# Frontpanel.net
KiCad netlist of a schematic drawn in Altium Designer
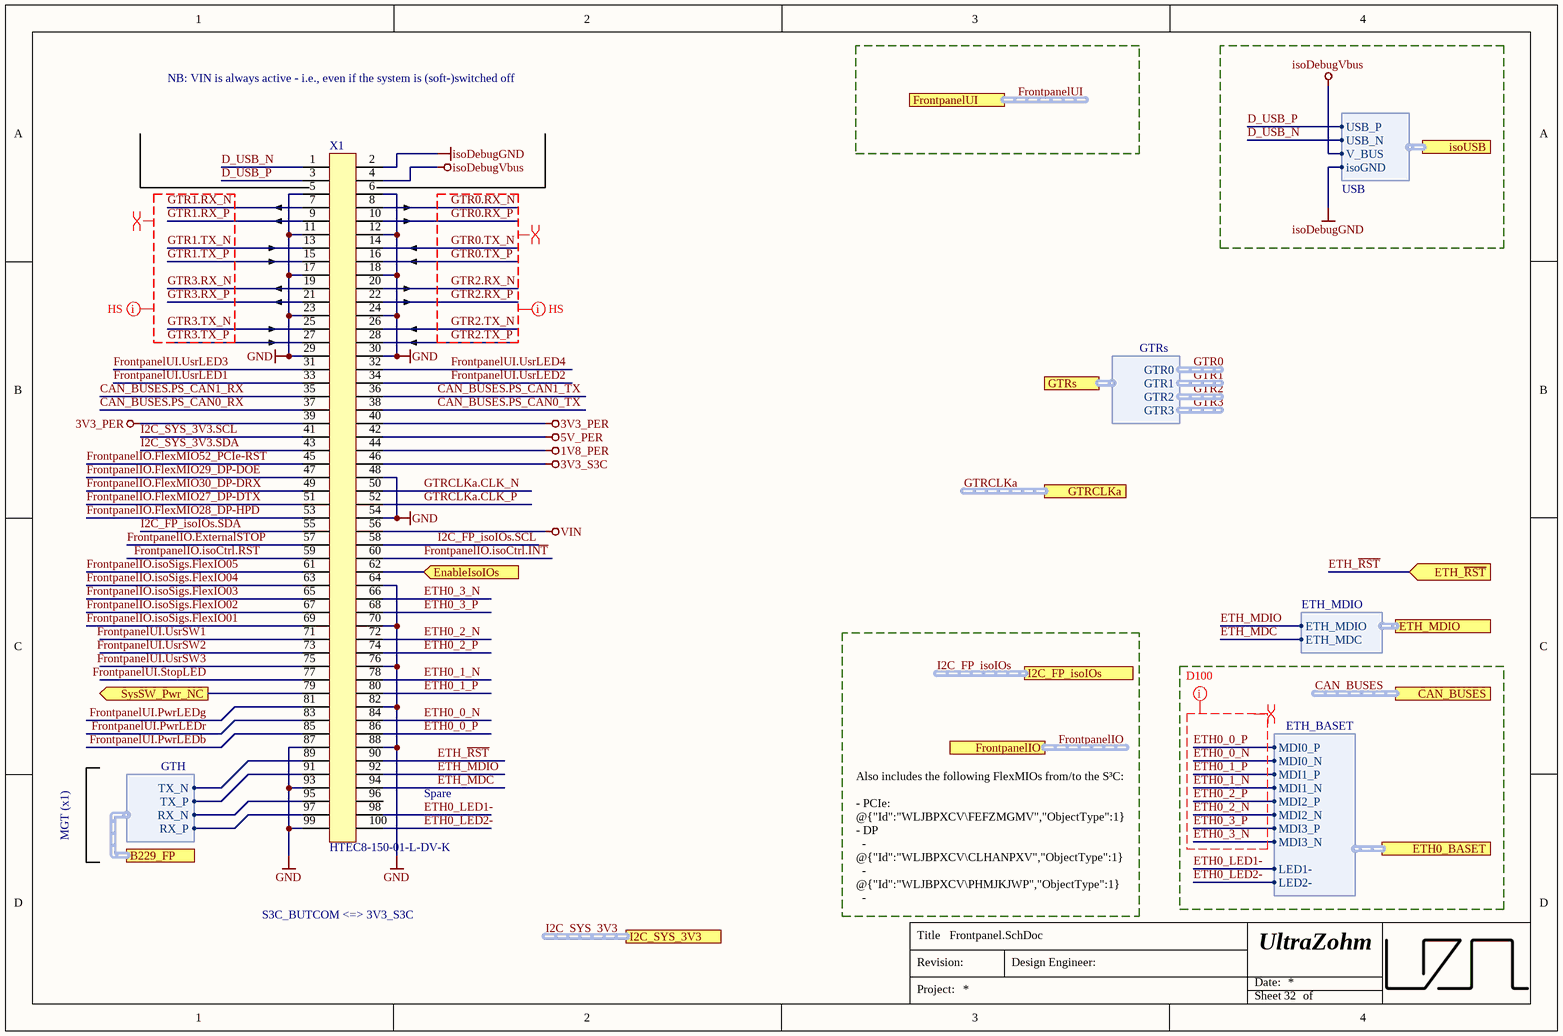
[diagram p0: Frontpanel.SchDoc]

(export (version "E")
  (design (tool "Eeschema 10.0.6"))
  (components
    (comp (ref "X1")
      (value "HTEC8-150-01-L-DV-K")
      (footprint "HTEC8-150-XX-X-DV")
      (description "HTEC8-150-01-L-DV-K mating connector for card layout")
      (fields
        (field (name "MANUFACTURER") "SAMTEC")
        (field (name "LCSC PART NUMBER") "C20365621")
        (field (name "CREATED FROM") "MGremer")
      )
      (libsource (lib "user") (part "HTEC8-150-01-L-DV-K"))
    )
  )
  (nets
    (net (code "14") (name "/CAN_BUSES.PS_CAN0_RX") (class "Default")
      (node (ref "X1") (pin "37") (pinfunction "37_37") (pintype "passive"))
    )
    (net (code "15") (name "/CAN_BUSES.PS_CAN0_TX") (class "Default")
      (node (ref "X1") (pin "38") (pinfunction "38_38") (pintype "passive"))
    )
    (net (code "16") (name "/CAN_BUSES.PS_CAN1_RX") (class "Default")
      (node (ref "X1") (pin "35") (pinfunction "35_35") (pintype "passive"))
    )
    (net (code "17") (name "/CAN_BUSES.PS_CAN1_TX") (class "Default")
      (node (ref "X1") (pin "36") (pinfunction "36_36") (pintype "passive"))
    )
    (net (code "18") (name "/D_USB_N") (class "Default")
      (node (ref "X1") (pin "1") (pinfunction "1_1") (pintype "passive"))
    )
    (net (code "19") (name "/D_USB_P") (class "Default")
      (node (ref "X1") (pin "3") (pinfunction "3_3") (pintype "passive"))
    )
    (net (code "20") (name "/ETH0_0_N") (class "Default")
      (node (ref "X1") (pin "84") (pinfunction "84_84") (pintype "passive"))
    )
    (net (code "21") (name "/ETH0_0_P") (class "Default")
      (node (ref "X1") (pin "86") (pinfunction "86_86") (pintype "passive"))
    )
    (net (code "22") (name "/ETH0_1_N") (class "Default")
      (node (ref "X1") (pin "78") (pinfunction "78_78") (pintype "passive"))
    )
    (net (code "23") (name "/ETH0_1_P") (class "Default")
      (node (ref "X1") (pin "80") (pinfunction "80_80") (pintype "passive"))
    )
    (net (code "24") (name "/ETH0_2_N") (class "Default")
      (node (ref "X1") (pin "72") (pinfunction "72_72") (pintype "passive"))
    )
    (net (code "25") (name "/ETH0_2_P") (class "Default")
      (node (ref "X1") (pin "74") (pinfunction "74_74") (pintype "passive"))
    )
    (net (code "26") (name "/ETH0_3_N") (class "Default")
      (node (ref "X1") (pin "66") (pinfunction "66_66") (pintype "passive"))
    )
    (net (code "27") (name "/ETH0_3_P") (class "Default")
      (node (ref "X1") (pin "68") (pinfunction "68_68") (pintype "passive"))
    )
    (net (code "28") (name "/ETH0_LED1-") (class "Default")
      (node (ref "X1") (pin "98") (pinfunction "98_98") (pintype "passive"))
    )
    (net (code "29") (name "/ETH0_LED2-") (class "Default")
      (node (ref "X1") (pin "100") (pinfunction "100_100") (pintype "passive"))
    )
    (net (code "30") (name "/ETH_MDC") (class "Default")
      (node (ref "X1") (pin "94") (pinfunction "94_94") (pintype "passive"))
    )
    (net (code "31") (name "/ETH_MDIO") (class "Default")
      (node (ref "X1") (pin "92") (pinfunction "92_92") (pintype "passive"))
    )
    (net (code "32") (name "/ETH_~{RST}") (class "Default")
      (node (ref "X1") (pin "90") (pinfunction "90_90") (pintype "passive"))
    )
    (net (code "33") (name "/EnableIsoIOs") (class "Default")
      (node (ref "X1") (pin "62") (pinfunction "62_62") (pintype "passive"))
    )
    (net (code "34") (name "/FrontpanelIO.ExternalSTOP") (class "Default")
      (node (ref "X1") (pin "57") (pinfunction "57_57") (pintype "passive"))
    )
    (net (code "35") (name "/FrontpanelIO.FlexMIO27_DP-DTX") (class "Default")
      (node (ref "X1") (pin "51") (pinfunction "51_51") (pintype "passive"))
    )
    (net (code "36") (name "/FrontpanelIO.FlexMIO28_DP-HPD") (class "Default")
      (node (ref "X1") (pin "53") (pinfunction "53_53") (pintype "passive"))
    )
    (net (code "37") (name "/FrontpanelIO.FlexMIO29_DP-DOE") (class "Default")
      (node (ref "X1") (pin "47") (pinfunction "47_47") (pintype "passive"))
    )
    (net (code "38") (name "/FrontpanelIO.FlexMIO30_DP-DRX") (class "Default")
      (node (ref "X1") (pin "49") (pinfunction "49_49") (pintype "passive"))
    )
    (net (code "39") (name "/FrontpanelIO.FlexMIO52_PCIe-~{RST}") (class "Default")
      (node (ref "X1") (pin "45") (pinfunction "45_45") (pintype "passive"))
    )
    (net (code "40") (name "/FrontpanelIO.isoCtrl.~{INT}") (class "Default")
      (node (ref "X1") (pin "60") (pinfunction "60_60") (pintype "passive"))
    )
    (net (code "41") (name "/FrontpanelIO.isoCtrl.~{RST}") (class "Default")
      (node (ref "X1") (pin "59") (pinfunction "59_59") (pintype "passive"))
    )
    (net (code "42") (name "/FrontpanelIO.isoSigs.FlexIO01") (class "Default")
      (node (ref "X1") (pin "69") (pinfunction "69_69") (pintype "passive"))
    )
    (net (code "43") (name "/FrontpanelIO.isoSigs.FlexIO02") (class "Default")
      (node (ref "X1") (pin "67") (pinfunction "67_67") (pintype "passive"))
    )
    (net (code "44") (name "/FrontpanelIO.isoSigs.FlexIO03") (class "Default")
      (node (ref "X1") (pin "65") (pinfunction "65_65") (pintype "passive"))
    )
    (net (code "45") (name "/FrontpanelIO.isoSigs.FlexIO04") (class "Default")
      (node (ref "X1") (pin "63") (pinfunction "63_63") (pintype "passive"))
    )
    (net (code "46") (name "/FrontpanelIO.isoSigs.FlexIO05") (class "Default")
      (node (ref "X1") (pin "61") (pinfunction "61_61") (pintype "passive"))
    )
    (net (code "47") (name "/FrontpanelUI.PwrLEDb") (class "Default")
      (node (ref "X1") (pin "85") (pinfunction "85_85") (pintype "passive"))
    )
    (net (code "48") (name "/FrontpanelUI.PwrLEDg") (class "Default")
      (node (ref "X1") (pin "81") (pinfunction "81_81") (pintype "passive"))
    )
    (net (code "49") (name "/FrontpanelUI.PwrLEDr") (class "Default")
      (node (ref "X1") (pin "83") (pinfunction "83_83") (pintype "passive"))
    )
    (net (code "50") (name "/FrontpanelUI.StopLED") (class "Default")
      (node (ref "X1") (pin "77") (pinfunction "77_77") (pintype "passive"))
    )
    (net (code "51") (name "/FrontpanelUI.UsrLED1") (class "Default")
      (node (ref "X1") (pin "33") (pinfunction "33_33") (pintype "passive"))
    )
    (net (code "52") (name "/FrontpanelUI.UsrLED2") (class "Default")
      (node (ref "X1") (pin "34") (pinfunction "34_34") (pintype "passive"))
    )
    (net (code "53") (name "/FrontpanelUI.UsrLED3") (class "Default")
      (node (ref "X1") (pin "31") (pinfunction "31_31") (pintype "passive"))
    )
    (net (code "54") (name "/FrontpanelUI.UsrLED4") (class "Default")
      (node (ref "X1") (pin "32") (pinfunction "32_32") (pintype "passive"))
    )
    (net (code "55") (name "/FrontpanelUI.UsrSW1") (class "Default")
      (node (ref "X1") (pin "71") (pinfunction "71_71") (pintype "passive"))
    )
    (net (code "56") (name "/FrontpanelUI.UsrSW2") (class "Default")
      (node (ref "X1") (pin "73") (pinfunction "73_73") (pintype "passive"))
    )
    (net (code "57") (name "/FrontpanelUI.UsrSW3") (class "Default")
      (node (ref "X1") (pin "75") (pinfunction "75_75") (pintype "passive"))
    )
    (net (code "58") (name "/GTR0.RX_N") (class "Default")
      (node (ref "X1") (pin "8") (pinfunction "8_8") (pintype "passive"))
    )
    (net (code "59") (name "/GTR0.RX_P") (class "Default")
      (node (ref "X1") (pin "10") (pinfunction "10_10") (pintype "passive"))
    )
    (net (code "60") (name "/GTR0.TX_N") (class "Default")
      (node (ref "X1") (pin "14") (pinfunction "14_14") (pintype "passive"))
    )
    (net (code "61") (name "/GTR0.TX_P") (class "Default")
      (node (ref "X1") (pin "16") (pinfunction "16_16") (pintype "passive"))
    )
    (net (code "62") (name "/GTR1.RX_N") (class "Default")
      (node (ref "X1") (pin "7") (pinfunction "7_7") (pintype "passive"))
    )
    (net (code "63") (name "/GTR1.RX_P") (class "Default")
      (node (ref "X1") (pin "9") (pinfunction "9_9") (pintype "passive"))
    )
    (net (code "64") (name "/GTR1.TX_N") (class "Default")
      (node (ref "X1") (pin "13") (pinfunction "13_13") (pintype "passive"))
    )
    (net (code "65") (name "/GTR1.TX_P") (class "Default")
      (node (ref "X1") (pin "15") (pinfunction "15_15") (pintype "passive"))
    )
    (net (code "66") (name "/GTR2.RX_N") (class "Default")
      (node (ref "X1") (pin "20") (pinfunction "20_20") (pintype "passive"))
    )
    (net (code "67") (name "/GTR2.RX_P") (class "Default")
      (node (ref "X1") (pin "22") (pinfunction "22_22") (pintype "passive"))
    )
    (net (code "68") (name "/GTR2.TX_N") (class "Default")
      (node (ref "X1") (pin "26") (pinfunction "26_26") (pintype "passive"))
    )
    (net (code "69") (name "/GTR2.TX_P") (class "Default")
      (node (ref "X1") (pin "28") (pinfunction "28_28") (pintype "passive"))
    )
    (net (code "70") (name "/GTR3.RX_N") (class "Default")
      (node (ref "X1") (pin "19") (pinfunction "19_19") (pintype "passive"))
    )
    (net (code "71") (name "/GTR3.RX_P") (class "Default")
      (node (ref "X1") (pin "21") (pinfunction "21_21") (pintype "passive"))
    )
    (net (code "72") (name "/GTR3.TX_N") (class "Default")
      (node (ref "X1") (pin "25") (pinfunction "25_25") (pintype "passive"))
    )
    (net (code "73") (name "/GTR3.TX_P") (class "Default")
      (node (ref "X1") (pin "27") (pinfunction "27_27") (pintype "passive"))
    )
    (net (code "75") (name "/GTRCLKa.CLK_N") (class "Default")
      (node (ref "X1") (pin "50") (pinfunction "50_50") (pintype "passive"))
    )
    (net (code "76") (name "/GTRCLKa.CLK_P") (class "Default")
      (node (ref "X1") (pin "52") (pinfunction "52_52") (pintype "passive"))
    )
    (net (code "78") (name "/I2C_FP_isoIOs.SCL") (class "Default")
      (node (ref "X1") (pin "58") (pinfunction "58_58") (pintype "passive"))
    )
    (net (code "79") (name "/I2C_FP_isoIOs.SDA") (class "Default")
      (node (ref "X1") (pin "55") (pinfunction "55_55") (pintype "passive"))
    )
    (net (code "80") (name "/I2C_SYS_3V3.SCL") (class "Default")
      (node (ref "X1") (pin "41") (pinfunction "41_41") (pintype "passive"))
    )
    (net (code "81") (name "/I2C_SYS_3V3.SDA") (class "Default")
      (node (ref "X1") (pin "43") (pinfunction "43_43") (pintype "passive"))
    )
    (net (code "82") (name "/RX_N") (class "Default")
      (node (ref "X1") (pin "95") (pinfunction "95_95") (pintype "passive"))
    )
    (net (code "83") (name "/RX_P") (class "Default")
      (node (ref "X1") (pin "97") (pinfunction "97_97") (pintype "passive"))
    )
    (net (code "84") (name "/SysSW_Pwr_NC") (class "Default")
      (node (ref "X1") (pin "79") (pinfunction "79_79") (pintype "passive"))
    )
    (net (code "85") (name "/TX_N") (class "Default")
      (node (ref "X1") (pin "89") (pinfunction "89_89") (pintype "passive"))
    )
    (net (code "86") (name "/TX_P") (class "Default")
      (node (ref "X1") (pin "91") (pinfunction "91_91") (pintype "passive"))
    )
    (net (code "99") (name "1V8_PER") (class "Default")
      (node (ref "X1") (pin "44") (pinfunction "44_44") (pintype "passive"))
    )
    (net (code "100") (name "3V3_PER") (class "Default")
      (node (ref "X1") (pin "39") (pinfunction "39_39") (pintype "passive"))
      (node (ref "X1") (pin "40") (pinfunction "40_40") (pintype "passive"))
    )
    (net (code "101") (name "3V3_S3C") (class "Default")
      (node (ref "X1") (pin "46") (pinfunction "46_46") (pintype "passive"))
    )
    (net (code "102") (name "5V_PER") (class "Default")
      (node (ref "X1") (pin "42") (pinfunction "42_42") (pintype "passive"))
    )
    (net (code "103") (name "GND") (class "Default")
      (node (ref "X1") (pin "11") (pinfunction "11_11") (pintype "passive"))
      (node (ref "X1") (pin "12") (pinfunction "12_12") (pintype "passive"))
      (node (ref "X1") (pin "17") (pinfunction "17_17") (pintype "passive"))
      (node (ref "X1") (pin "18") (pinfunction "18_18") (pintype "passive"))
      (node (ref "X1") (pin "23") (pinfunction "23_23") (pintype "passive"))
      (node (ref "X1") (pin "24") (pinfunction "24_24") (pintype "passive"))
      (node (ref "X1") (pin "29") (pinfunction "29_29") (pintype "passive"))
      (node (ref "X1") (pin "30") (pinfunction "30_30") (pintype "passive"))
      (node (ref "X1") (pin "48") (pinfunction "48_48") (pintype "passive"))
      (node (ref "X1") (pin "5") (pinfunction "5_5") (pintype "passive"))
      (node (ref "X1") (pin "54") (pinfunction "54_54") (pintype "passive"))
      (node (ref "X1") (pin "6") (pinfunction "6_6") (pintype "passive"))
      (node (ref "X1") (pin "64") (pinfunction "64_64") (pintype "passive"))
      (node (ref "X1") (pin "70") (pinfunction "70_70") (pintype "passive"))
      (node (ref "X1") (pin "76") (pinfunction "76_76") (pintype "passive"))
      (node (ref "X1") (pin "82") (pinfunction "82_82") (pintype "passive"))
      (node (ref "X1") (pin "87") (pinfunction "87_87") (pintype "passive"))
      (node (ref "X1") (pin "88") (pinfunction "88_88") (pintype "passive"))
      (node (ref "X1") (pin "93") (pinfunction "93_93") (pintype "passive"))
      (node (ref "X1") (pin "99") (pinfunction "99_99") (pintype "passive"))
    )
    (net (code "104") (name "VIN") (class "Default")
      (node (ref "X1") (pin "56") (pinfunction "56_56") (pintype "passive"))
    )
    (net (code "105") (name "isoDebugGND") (class "Default")
      (node (ref "X1") (pin "2") (pinfunction "2_2") (pintype "passive"))
    )
    (net (code "106") (name "isoDebugVbus") (class "Default")
      (node (ref "X1") (pin "4") (pinfunction "4_4") (pintype "passive"))
    )
    (net (code "107") (name "unconnected-(X1-Pad96)") (class "Default")
      (node (ref "X1") (pin "96") (pinfunction "96_96") (pintype "passive"))
    )
  )
)
